# mx25u1633f-breakout.net
KiCad netlist of a schematic drawn in EAGLE
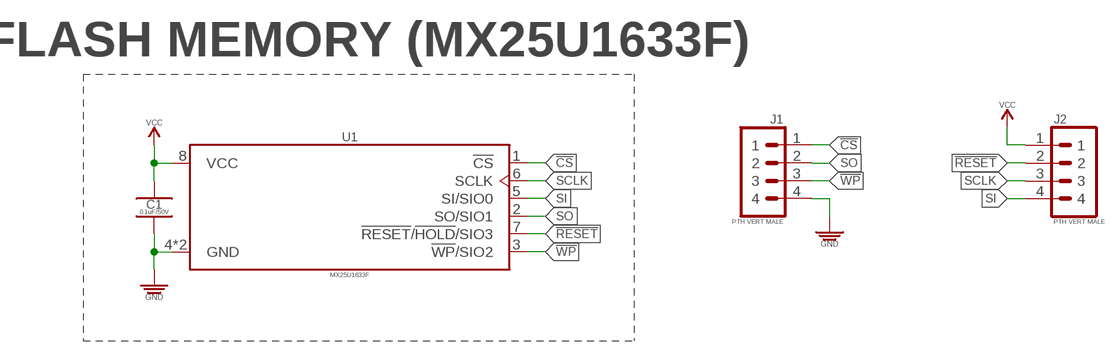
[diagram p0: schematic, sheet 1]

(export (version "E")
  (design (tool "Eeschema 10.0.6"))
  (components
    (comp (ref "C1")
      (value "0.1uF/50V")
      (footprint "eagle-import:CAPC1005X55_SMD-0402")
      (fields (field (name "MFR") "TDK Corporation") (field (name "MPN") "C1005X7R1H104K050BE"))
      (libsource (lib "eagle-import") (part "0.1UF_SMD-0402_50V-10%"))
    )
    (comp (ref "J1")
      (value "PTH VERT MALE")
      (footprint "eagle-import:HDRV4W64P254_1X4_1016X254X838B")
      (fields (field (name "MFR") "Sullins Connector Solutions") (field (name "MPN") "PEC04SAAN"))
      (libsource (lib "eagle-import") (part "1X04_PTH_VERT_MALE_2.54MM"))
    )
    (comp (ref "J2")
      (value "PTH VERT MALE")
      (footprint "eagle-import:HDRV4W64P254_1X4_1016X254X838B")
      (fields (field (name "MFR") "Sullins Connector Solutions") (field (name "MPN") "PEC04SAAN"))
      (libsource (lib "eagle-import") (part "1X04_PTH_VERT_MALE_2.54MM"))
    )
    (comp (ref "U1")
      (value "MX25U1633F")
      (footprint "eagle-import:SON50P300X200X55-9T20X160N")
      (fields (field (name "MFR") "Macronix") (field (name "MPN") "MX25U1633FZUI"))
      (libsource (lib "eagle-import") (part "MX25U1633F"))
    )
  )
  (nets
    (net (code "1") (name "/~{CS}") (class "Default")
      (node (ref "J1") (pin "1") (pinfunction "1_1") (pintype "passive"))
      (node (ref "U1") (pin "1") (pinfunction "~{CS}_1") (pintype "bidirectional"))
    )
    (net (code "2") (name "/~{RESET}") (class "Default")
      (node (ref "J2") (pin "2") (pinfunction "2_2") (pintype "passive"))
      (node (ref "U1") (pin "7") (pinfunction "~{RESET}/~{HOLD}/SIO3_7") (pintype "bidirectional"))
    )
    (net (code "3") (name "/~{WP}") (class "Default")
      (node (ref "J1") (pin "3") (pinfunction "3_3") (pintype "passive"))
      (node (ref "U1") (pin "3") (pinfunction "~{WP}/SIO2_3") (pintype "bidirectional"))
    )
    (net (code "4") (name "GND") (class "Default")
      (node (ref "C1") (pin "2") (pinfunction "2_2") (pintype "passive"))
      (node (ref "J1") (pin "4") (pinfunction "4_4") (pintype "passive"))
      (node (ref "U1") (pin "4") (pinfunction "GND_4") (pintype "power_in"))
      (node (ref "U1") (pin "EP") (pinfunction "GND_EP") (pintype "power_in"))
    )
    (net (code "5") (name "SCLK") (class "Default")
      (node (ref "J2") (pin "3") (pinfunction "3_3") (pintype "passive"))
      (node (ref "U1") (pin "6") (pinfunction "SCLK_6") (pintype "input"))
    )
    (net (code "6") (name "SI") (class "Default")
      (node (ref "J2") (pin "4") (pinfunction "4_4") (pintype "passive"))
      (node (ref "U1") (pin "5") (pinfunction "SI/SIO0_5") (pintype "bidirectional"))
    )
    (net (code "7") (name "SO") (class "Default")
      (node (ref "J1") (pin "2") (pinfunction "2_2") (pintype "passive"))
      (node (ref "U1") (pin "2") (pinfunction "SO/SIO1_2") (pintype "bidirectional"))
    )
    (net (code "8") (name "VCC") (class "Default")
      (node (ref "C1") (pin "1") (pinfunction "1_1") (pintype "passive"))
      (node (ref "J2") (pin "1") (pinfunction "1_1") (pintype "passive"))
      (node (ref "U1") (pin "8") (pinfunction "VCC_8") (pintype "power_in"))
    )
  )
)
